# 01_USB_Isolator.net
KiCad netlist of a schematic drawn in Altium Designer
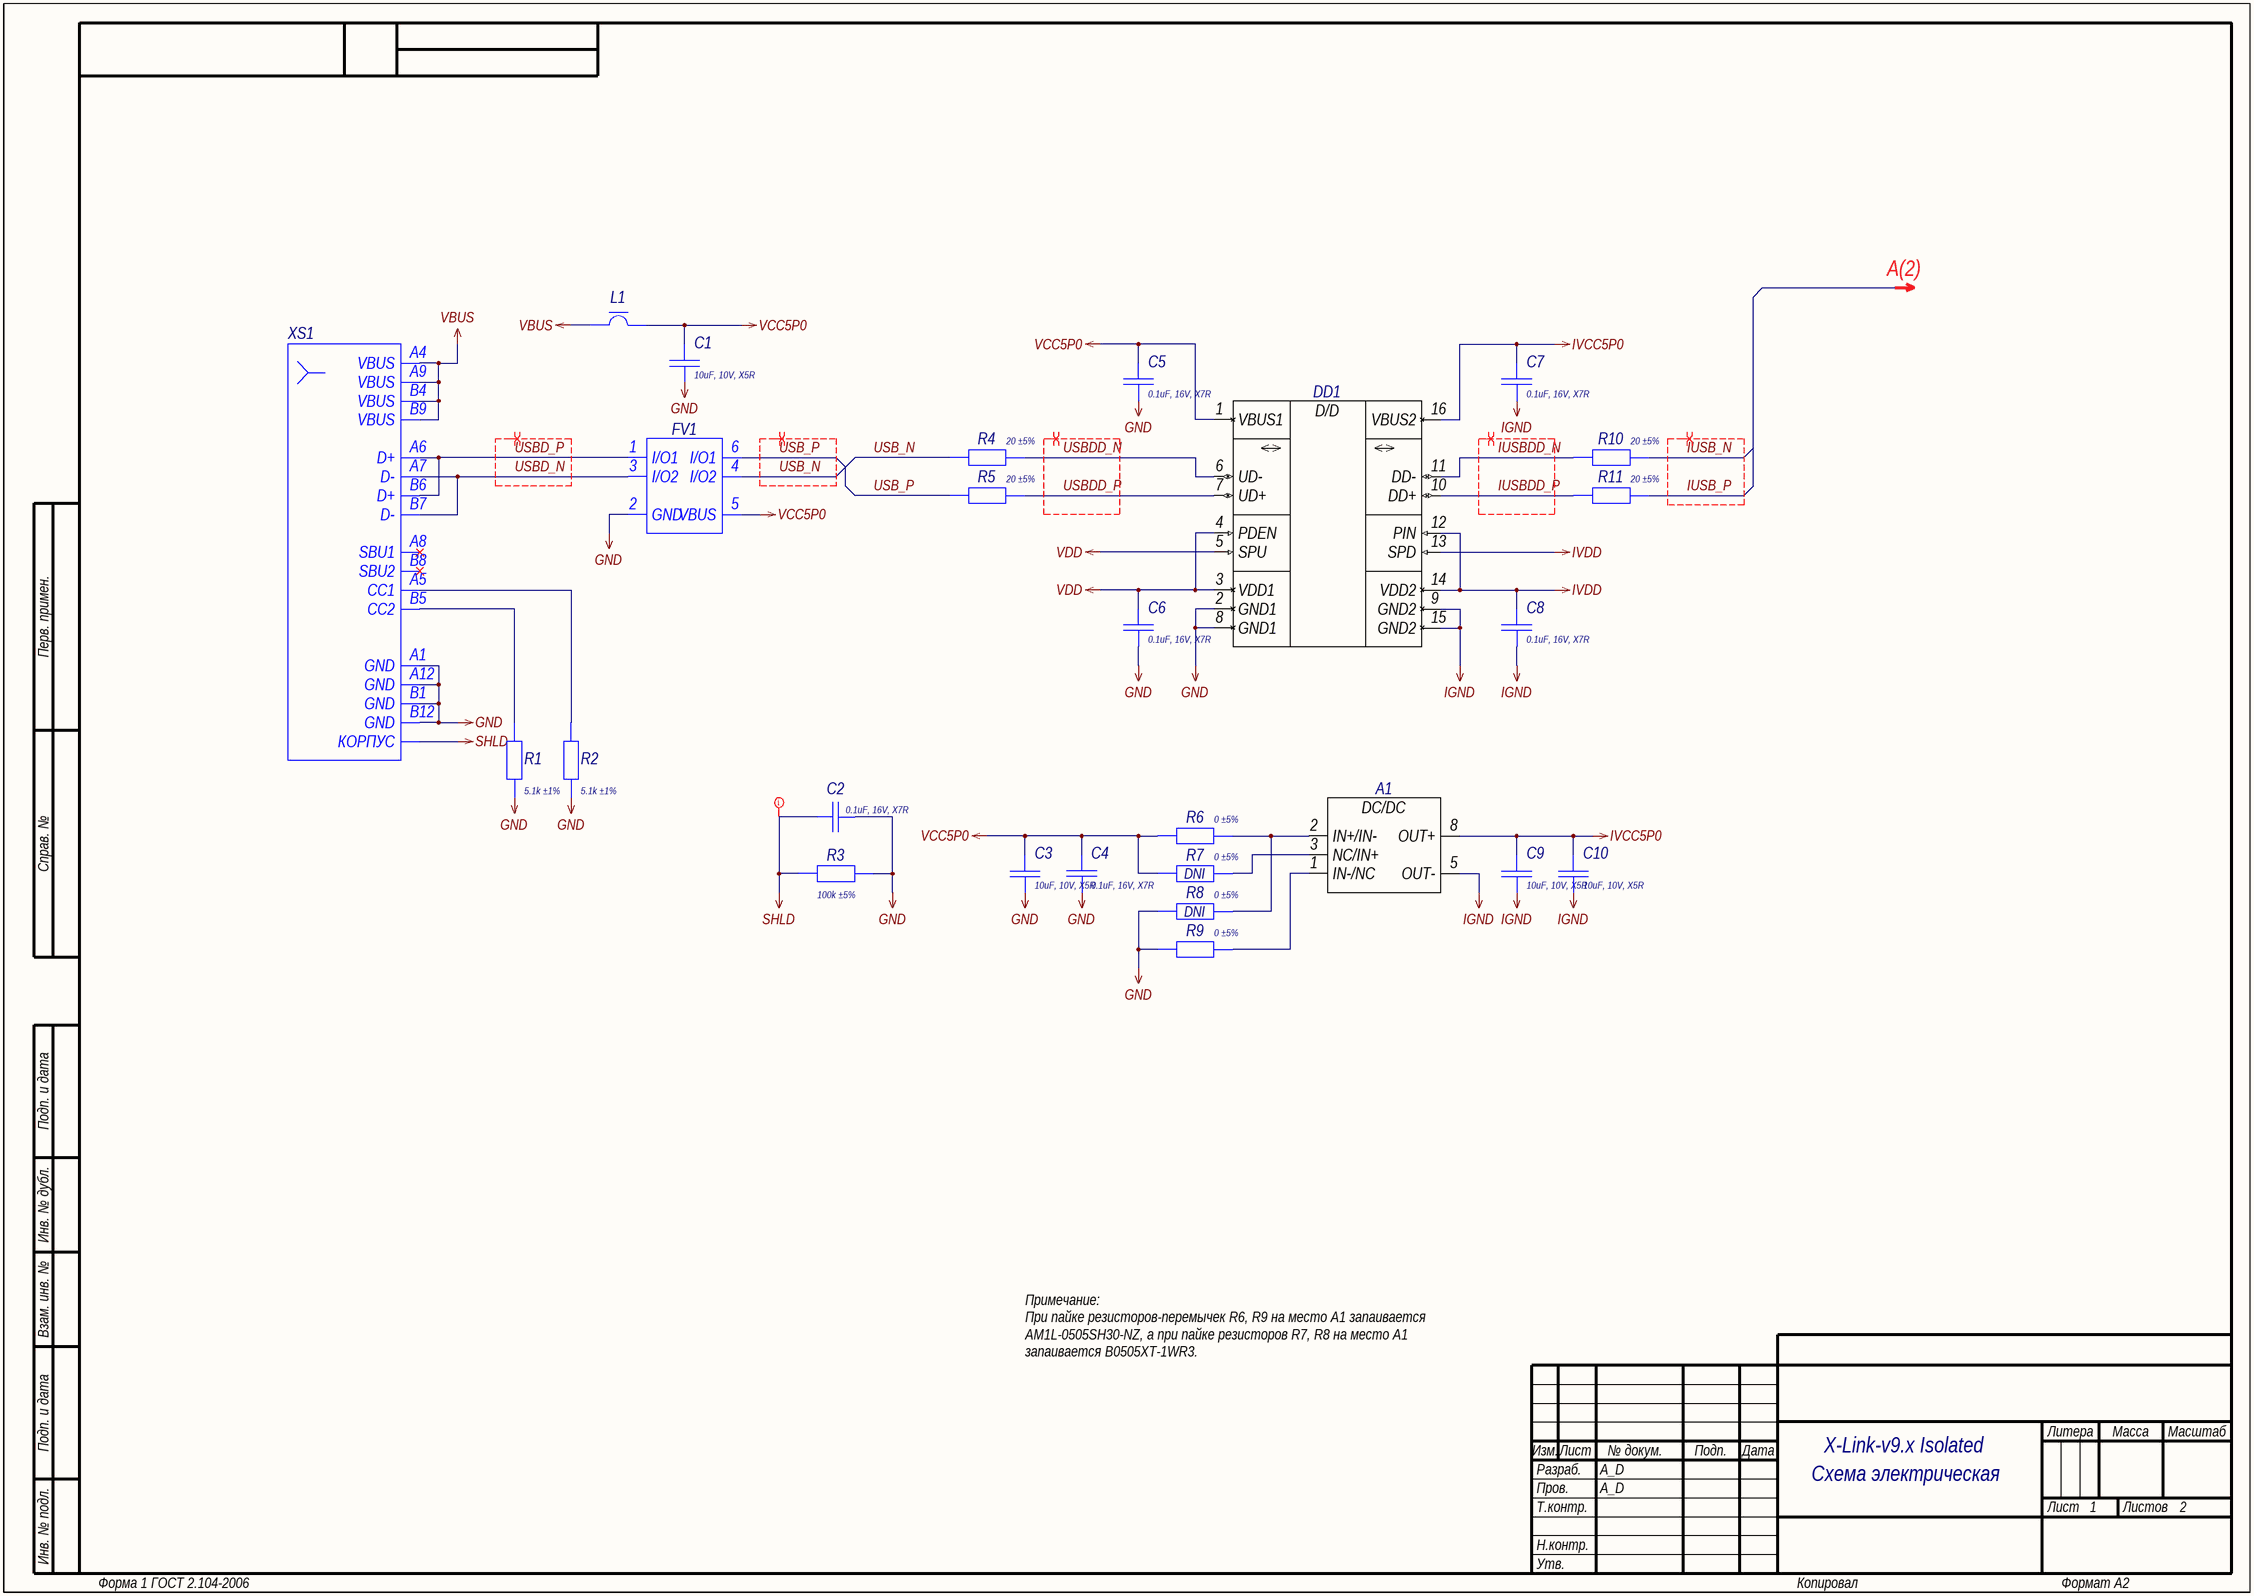
[diagram p0: 01_USB Isolator.SchDoc]

(export (version "E")
  (design (tool "Eeschema 10.0.6"))
  (components
    (comp (ref "A1")
      (value "AM1L-xxxxSH30-Series")
      (footprint "AM1L-xxxxSH30-Series")
      (fields
        (field (name "PART NUMBER") "AM1L-0505SH30-NZ")
        (field (name "MANUFACTURER") "Aimtec")
        (field (name "PUBLISHER") "Andrew Danich")
      )
      (libsource (lib "ADLib") (part "AM1L-xxxxSH30-Series"))
    )
    (comp (ref "C1")
      (value "Capacitor")
      (footprint "C0603_L")
      (fields
        (field (name "PART NUMBER") "GRM188R61A106KE69D")
        (field (name "VOLTAGE") "10V")
        (field (name "TOLERANCE") "±10%")
        (field (name "SCHEMATIC VALUE") "10uF, 10V, X5R")
        (field (name "PUBLISHER") "Andrew Danich")
      )
      (libsource (lib "ADLib") (part "Capacitor"))
    )
    (comp (ref "C2")
      (value "Capacitor")
      (footprint "C0402_L")
      (fields
        (field (name "PART NUMBER") "GCM155R71C104KA55D")
        (field (name "VOLTAGE") "16V")
        (field (name "TOLERANCE") "±10%")
        (field (name "SCHEMATIC VALUE") "0.1uF, 16V, X7R")
        (field (name "PUBLISHER") "Andrew Danich")
      )
      (libsource (lib "ADLib") (part "Capacitor"))
    )
    (comp (ref "C3")
      (value "Capacitor")
      (footprint "C0603_L")
      (fields
        (field (name "PART NUMBER") "GRM188R61A106KE69D")
        (field (name "VOLTAGE") "10V")
        (field (name "TOLERANCE") "±10%")
        (field (name "SCHEMATIC VALUE") "10uF, 10V, X5R")
        (field (name "PUBLISHER") "Andrew Danich")
      )
      (libsource (lib "ADLib") (part "Capacitor"))
    )
    (comp (ref "C4")
      (value "Capacitor")
      (footprint "C0402_L")
      (fields
        (field (name "PART NUMBER") "GCM155R71C104KA55D")
        (field (name "VOLTAGE") "16V")
        (field (name "TOLERANCE") "±10%")
        (field (name "SCHEMATIC VALUE") "0.1uF, 16V, X7R")
        (field (name "PUBLISHER") "Andrew Danich")
      )
      (libsource (lib "ADLib") (part "Capacitor"))
    )
    (comp (ref "C5")
      (value "Capacitor")
      (footprint "C0402_L")
      (fields
        (field (name "PART NUMBER") "GCM155R71C104KA55D")
        (field (name "VOLTAGE") "16V")
        (field (name "TOLERANCE") "±10%")
        (field (name "SCHEMATIC VALUE") "0.1uF, 16V, X7R")
        (field (name "PUBLISHER") "Andrew Danich")
      )
      (libsource (lib "ADLib") (part "Capacitor"))
    )
    (comp (ref "C6")
      (value "Capacitor")
      (footprint "C0402_L")
      (fields
        (field (name "PART NUMBER") "GCM155R71C104KA55D")
        (field (name "VOLTAGE") "16V")
        (field (name "TOLERANCE") "±10%")
        (field (name "SCHEMATIC VALUE") "0.1uF, 16V, X7R")
        (field (name "PUBLISHER") "Andrew Danich")
      )
      (libsource (lib "ADLib") (part "Capacitor"))
    )
    (comp (ref "C7")
      (value "Capacitor")
      (footprint "C0402_L")
      (fields
        (field (name "PART NUMBER") "GCM155R71C104KA55D")
        (field (name "VOLTAGE") "16V")
        (field (name "TOLERANCE") "±10%")
        (field (name "SCHEMATIC VALUE") "0.1uF, 16V, X7R")
        (field (name "PUBLISHER") "Andrew Danich")
      )
      (libsource (lib "ADLib") (part "Capacitor"))
    )
    (comp (ref "C8")
      (value "Capacitor")
      (footprint "C0402_L")
      (fields
        (field (name "PART NUMBER") "GCM155R71C104KA55D")
        (field (name "VOLTAGE") "16V")
        (field (name "TOLERANCE") "±10%")
        (field (name "SCHEMATIC VALUE") "0.1uF, 16V, X7R")
        (field (name "PUBLISHER") "Andrew Danich")
      )
      (libsource (lib "ADLib") (part "Capacitor"))
    )
    (comp (ref "C9")
      (value "Capacitor")
      (footprint "C0603_L")
      (fields
        (field (name "PART NUMBER") "GRM188R61A106KE69D")
        (field (name "VOLTAGE") "10V")
        (field (name "TOLERANCE") "±10%")
        (field (name "SCHEMATIC VALUE") "10uF, 10V, X5R")
        (field (name "PUBLISHER") "Andrew Danich")
      )
      (libsource (lib "ADLib") (part "Capacitor"))
    )
    (comp (ref "C10")
      (value "Capacitor")
      (footprint "C0603_L")
      (fields
        (field (name "PART NUMBER") "GRM188R61A106KE69D")
        (field (name "VOLTAGE") "10V")
        (field (name "TOLERANCE") "±10%")
        (field (name "SCHEMATIC VALUE") "10uF, 10V, X5R")
        (field (name "PUBLISHER") "Andrew Danich")
      )
      (libsource (lib "ADLib") (part "Capacitor"))
    )
    (comp (ref "DD1")
      (value "ADuMx160-Series")
      (footprint "SOIC-16_127P1030X750X265_N")
      (fields
        (field (name "PART NUMBER") "ADUM3160BRWZ")
        (field (name "MANUFACTURER") "Analog Devices")
        (field (name "PUBLISHER") "Andrew Danich")
      )
      (libsource (lib "ADLib") (part "ADuMx160-Series"))
    )
    (comp (ref "FV1")
      (value "USBLC6-2x6")
      (footprint "SOT-666_050P160X120X060_N")
      (fields
        (field (name "PART NUMBER") "USBLC6-2P6")
        (field (name "MANUFACTURER") "STMicroelectronics")
        (field (name "PUBLISHER") "Andrew Danich")
      )
      (libsource (lib "ADLib") (part "USBLC6-2x6"))
    )
    (comp (ref "L1")
      (value "FerriteBead")
      (footprint "L0402_L")
      (fields
        (field (name "PART NUMBER") "BLM15PD121SN1D")
        (field (name "TOLERANCE") "±25%")
        (field (name "MANUFACTURER") "Murata")
        (field (name "PUBLISHER") "Andrew Danich")
      )
      (libsource (lib "ADLib") (part "FerriteBead"))
    )
    (comp (ref "R1")
      (value "Resistor")
      (footprint "R0402_L")
      (fields
        (field (name "PART NUMBER") "RC0402FR-075K1L")
        (field (name "TOLERANCE") "±1%")
        (field (name "MANUFACTURER") "Yageo")
        (field (name "SCHEMATIC VALUE") "5.1k ±1%")
        (field (name "PUBLISHER") "Andrew Danich")
      )
      (libsource (lib "ADLib") (part "Resistor"))
    )
    (comp (ref "R2")
      (value "Resistor")
      (footprint "R0402_L")
      (fields
        (field (name "PART NUMBER") "RC0402FR-075K1L")
        (field (name "TOLERANCE") "±1%")
        (field (name "MANUFACTURER") "Yageo")
        (field (name "SCHEMATIC VALUE") "5.1k ±1%")
        (field (name "PUBLISHER") "Andrew Danich")
      )
      (libsource (lib "ADLib") (part "Resistor"))
    )
    (comp (ref "R3")
      (value "Resistor")
      (footprint "R0402_L")
      (fields
        (field (name "PART NUMBER") "RC0402JR-07100KL")
        (field (name "TOLERANCE") "±5%")
        (field (name "MANUFACTURER") "Yageo")
        (field (name "SCHEMATIC VALUE") "100k ±5%")
        (field (name "PUBLISHER") "Andrew Danich")
      )
      (libsource (lib "ADLib") (part "Resistor"))
    )
    (comp (ref "R4")
      (value "Resistor")
      (footprint "R0402_L")
      (fields
        (field (name "PART NUMBER") "RC0402JR-0720RL")
        (field (name "TOLERANCE") "±5%")
        (field (name "MANUFACTURER") "Yageo")
        (field (name "SCHEMATIC VALUE") "20 ±5%")
        (field (name "PUBLISHER") "Andrew Danich")
      )
      (libsource (lib "ADLib") (part "Resistor"))
    )
    (comp (ref "R5")
      (value "Resistor")
      (footprint "R0402_L")
      (fields
        (field (name "PART NUMBER") "RC0402JR-0720RL")
        (field (name "TOLERANCE") "±5%")
        (field (name "MANUFACTURER") "Yageo")
        (field (name "SCHEMATIC VALUE") "20 ±5%")
        (field (name "PUBLISHER") "Andrew Danich")
      )
      (libsource (lib "ADLib") (part "Resistor"))
    )
    (comp (ref "R6")
      (value "Resistor")
      (footprint "R0402_L")
      (fields
        (field (name "PART NUMBER") "RC0402JR-070RL")
        (field (name "TOLERANCE") "±5%")
        (field (name "MANUFACTURER") "Yageo")
        (field (name "SCHEMATIC VALUE") "0 ±5%")
        (field (name "PUBLISHER") "Andrew Danich")
      )
      (libsource (lib "ADLib") (part "Resistor"))
    )
    (comp (ref "R7")
      (value "Resistor")
      (footprint "R0402_L")
      (fields
        (field (name "PART NUMBER") "RC0402JR-070RL")
        (field (name "TOLERANCE") "±5%")
        (field (name "MANUFACTURER") "Yageo")
        (field (name "SCHEMATIC VALUE") "0 ±5%")
        (field (name "PUBLISHER") "Andrew Danich")
      )
      (libsource (lib "ADLib") (part "Resistor"))
    )
    (comp (ref "R8")
      (value "Resistor")
      (footprint "R0402_L")
      (fields
        (field (name "PART NUMBER") "RC0402JR-070RL")
        (field (name "TOLERANCE") "±5%")
        (field (name "MANUFACTURER") "Yageo")
        (field (name "SCHEMATIC VALUE") "0 ±5%")
        (field (name "PUBLISHER") "Andrew Danich")
      )
      (libsource (lib "ADLib") (part "Resistor"))
    )
    (comp (ref "R9")
      (value "Resistor")
      (footprint "R0402_L")
      (fields
        (field (name "PART NUMBER") "RC0402JR-070RL")
        (field (name "TOLERANCE") "±5%")
        (field (name "MANUFACTURER") "Yageo")
        (field (name "SCHEMATIC VALUE") "0 ±5%")
        (field (name "PUBLISHER") "Andrew Danich")
      )
      (libsource (lib "ADLib") (part "Resistor"))
    )
    (comp (ref "R10")
      (value "Resistor")
      (footprint "R0402_L")
      (fields
        (field (name "PART NUMBER") "RC0402JR-0720RL")
        (field (name "TOLERANCE") "±5%")
        (field (name "MANUFACTURER") "Yageo")
        (field (name "SCHEMATIC VALUE") "20 ±5%")
        (field (name "PUBLISHER") "Andrew Danich")
      )
      (libsource (lib "ADLib") (part "Resistor"))
    )
    (comp (ref "R11")
      (value "Resistor")
      (footprint "R0402_L")
      (fields
        (field (name "PART NUMBER") "RC0402JR-0720RL")
        (field (name "TOLERANCE") "±5%")
        (field (name "MANUFACTURER") "Yageo")
        (field (name "SCHEMATIC VALUE") "20 ±5%")
        (field (name "PUBLISHER") "Andrew Danich")
      )
      (libsource (lib "ADLib") (part "Resistor"))
    )
    (comp (ref "XS1")
      (value "Text")
      (footprint "U262-161N-4BVC11")
      (fields
        (field (name "PART NUMBER") "U262-161N-4BVC11")
        (field (name "MANUFACTURER") "XKB Enterprise")
        (field (name "PUBLISHER") "Andrew Danich")
      )
      (libsource (lib "ADLib") (part "Con-USB_C-F-16P"))
    )
  )
  (nets
    (net (code "1") (name "/IUSBDD_N") (class "Default")
      (node (ref "DD1") (pin "11") (pinfunction "DD-_11") (pintype "bidirectional"))
      (node (ref "R10") (pin "1") (pinfunction "1_1") (pintype "passive"))
    )
    (net (code "2") (name "/IUSBDD_P") (class "Default")
      (node (ref "DD1") (pin "10") (pinfunction "DD+_10") (pintype "bidirectional"))
      (node (ref "R11") (pin "1") (pinfunction "1_1") (pintype "passive"))
    )
    (net (code "3") (name "/IUSB_N") (class "Default")
      (node (ref "R10") (pin "2") (pinfunction "2_2") (pintype "passive"))
    )
    (net (code "4") (name "/IUSB_P") (class "Default")
      (node (ref "R11") (pin "2") (pinfunction "2_2") (pintype "passive"))
    )
    (net (code "5") (name "/USBDD_N") (class "Default")
      (node (ref "DD1") (pin "6") (pinfunction "UD-_6") (pintype "bidirectional"))
      (node (ref "R4") (pin "2") (pinfunction "2_2") (pintype "passive"))
    )
    (net (code "6") (name "/USBDD_P") (class "Default")
      (node (ref "DD1") (pin "7") (pinfunction "UD+_7") (pintype "bidirectional"))
      (node (ref "R5") (pin "2") (pinfunction "2_2") (pintype "passive"))
    )
    (net (code "7") (name "/USBD_N") (class "Default")
      (node (ref "FV1") (pin "3") (pinfunction "I/O2_3") (pintype "passive"))
      (node (ref "XS1") (pin "A7") (pinfunction "D-_A7") (pintype "passive"))
      (node (ref "XS1") (pin "B7") (pinfunction "D-_B7") (pintype "passive"))
    )
    (net (code "8") (name "/USBD_P") (class "Default")
      (node (ref "FV1") (pin "1") (pinfunction "I/O1_1") (pintype "passive"))
      (node (ref "XS1") (pin "A6") (pinfunction "D+_A6") (pintype "passive"))
      (node (ref "XS1") (pin "B6") (pinfunction "D+_B6") (pintype "passive"))
    )
    (net (code "9") (name "/USB_N") (class "Default")
      (node (ref "FV1") (pin "4") (pinfunction "I/O2_4") (pintype "passive"))
      (node (ref "R4") (pin "1") (pinfunction "1_1") (pintype "passive"))
    )
    (net (code "10") (name "/USB_P") (class "Default")
      (node (ref "FV1") (pin "6") (pinfunction "I/O1_6") (pintype "passive"))
      (node (ref "R5") (pin "1") (pinfunction "1_1") (pintype "passive"))
    )
    (net (code "11") (name "GND") (class "Default")
      (node (ref "C1") (pin "1") (pinfunction "1_1") (pintype "passive"))
      (node (ref "C2") (pin "1") (pinfunction "1_1") (pintype "passive"))
      (node (ref "C3") (pin "1") (pinfunction "1_1") (pintype "passive"))
      (node (ref "C4") (pin "2") (pinfunction "2_2") (pintype "passive"))
      (node (ref "C5") (pin "2") (pinfunction "2_2") (pintype "passive"))
      (node (ref "C6") (pin "2") (pinfunction "2_2") (pintype "passive"))
      (node (ref "DD1") (pin "2") (pinfunction "GND1_2") (pintype "power_in"))
      (node (ref "DD1") (pin "8") (pinfunction "GND1_8") (pintype "power_in"))
      (node (ref "FV1") (pin "2") (pinfunction "GND_2") (pintype "passive"))
      (node (ref "R1") (pin "1") (pinfunction "1_1") (pintype "passive"))
      (node (ref "R2") (pin "1") (pinfunction "1_1") (pintype "passive"))
      (node (ref "R3") (pin "2") (pinfunction "2_2") (pintype "passive"))
      (node (ref "R8") (pin "1") (pinfunction "1_1") (pintype "passive"))
      (node (ref "R9") (pin "1") (pinfunction "1_1") (pintype "passive"))
      (node (ref "XS1") (pin "A1") (pinfunction "GND_A1") (pintype "passive"))
      (node (ref "XS1") (pin "A12") (pinfunction "GND_A12") (pintype "passive"))
      (node (ref "XS1") (pin "B1") (pinfunction "GND_B1") (pintype "passive"))
      (node (ref "XS1") (pin "B12") (pinfunction "GND_B12") (pintype "passive"))
    )
    (net (code "12") (name "IGND") (class "Default")
      (node (ref "A1") (pin "5") (pinfunction "OUT-_5") (pintype "power_in"))
      (node (ref "C10") (pin "1") (pinfunction "1_1") (pintype "passive"))
      (node (ref "C7") (pin "2") (pinfunction "2_2") (pintype "passive"))
      (node (ref "C8") (pin "2") (pinfunction "2_2") (pintype "passive"))
      (node (ref "C9") (pin "1") (pinfunction "1_1") (pintype "passive"))
      (node (ref "DD1") (pin "15") (pinfunction "GND2_15") (pintype "power_in"))
      (node (ref "DD1") (pin "9") (pinfunction "GND2_9") (pintype "power_in"))
    )
    (net (code "13") (name "IVCC5P0") (class "Default")
      (node (ref "A1") (pin "8") (pinfunction "OUT+_8") (pintype "power_in"))
      (node (ref "C10") (pin "2") (pinfunction "2_2") (pintype "passive"))
      (node (ref "C7") (pin "1") (pinfunction "1_1") (pintype "passive"))
      (node (ref "C9") (pin "2") (pinfunction "2_2") (pintype "passive"))
      (node (ref "DD1") (pin "16") (pinfunction "VBUS2_16") (pintype "power_in"))
    )
    (net (code "14") (name "IVDD") (class "Default")
      (node (ref "C8") (pin "1") (pinfunction "1_1") (pintype "passive"))
      (node (ref "DD1") (pin "12") (pinfunction "PIN_12") (pintype "input"))
      (node (ref "DD1") (pin "13") (pinfunction "SPD_13") (pintype "input"))
      (node (ref "DD1") (pin "14") (pinfunction "VDD2_14") (pintype "power_in"))
    )
    (net (code "15") (name "Net-(A1-IN+{slash}IN-)") (class "Default")
      (node (ref "A1") (pin "2") (pinfunction "IN+/IN-_2") (pintype "power_in"))
      (node (ref "R6") (pin "2") (pinfunction "2_2") (pintype "passive"))
      (node (ref "R8") (pin "2") (pinfunction "2_2") (pintype "passive"))
    )
    (net (code "16") (name "Net-(A1-IN-{slash}NC)") (class "Default")
      (node (ref "A1") (pin "1") (pinfunction "IN-/NC_1") (pintype "power_in"))
      (node (ref "R9") (pin "2") (pinfunction "2_2") (pintype "passive"))
    )
    (net (code "17") (name "Net-(A1-NC{slash}IN+)") (class "Default")
      (node (ref "A1") (pin "3") (pinfunction "NC/IN+_3") (pintype "passive"))
      (node (ref "R7") (pin "2") (pinfunction "2_2") (pintype "passive"))
    )
    (net (code "18") (name "Net-(XS1-CC1)") (class "Default")
      (node (ref "R2") (pin "2") (pinfunction "2_2") (pintype "passive"))
      (node (ref "XS1") (pin "A5") (pinfunction "CC1_A5") (pintype "passive"))
    )
    (net (code "19") (name "Net-(XS1-CC2)") (class "Default")
      (node (ref "R1") (pin "2") (pinfunction "2_2") (pintype "passive"))
      (node (ref "XS1") (pin "B5") (pinfunction "CC2_B5") (pintype "passive"))
    )
    (net (code "20") (name "SHLD") (class "Default")
      (node (ref "C2") (pin "2") (pinfunction "2_2") (pintype "passive"))
      (node (ref "R3") (pin "1") (pinfunction "1_1") (pintype "passive"))
      (node (ref "XS1") (pin "SH") (pinfunction "КОРПУС_SH") (pintype "passive"))
    )
    (net (code "21") (name "VBUS") (class "Default")
      (node (ref "L1") (pin "1") (pinfunction "1_1") (pintype "passive"))
      (node (ref "XS1") (pin "A4") (pinfunction "VBUS_A4") (pintype "passive"))
      (node (ref "XS1") (pin "A9") (pinfunction "VBUS_A9") (pintype "passive"))
      (node (ref "XS1") (pin "B4") (pinfunction "VBUS_B4") (pintype "passive"))
      (node (ref "XS1") (pin "B9") (pinfunction "VBUS_B9") (pintype "passive"))
    )
    (net (code "22") (name "VCC5P0") (class "Default")
      (node (ref "C1") (pin "2") (pinfunction "2_2") (pintype "passive"))
      (node (ref "C3") (pin "2") (pinfunction "2_2") (pintype "passive"))
      (node (ref "C4") (pin "1") (pinfunction "1_1") (pintype "passive"))
      (node (ref "C5") (pin "1") (pinfunction "1_1") (pintype "passive"))
      (node (ref "DD1") (pin "1") (pinfunction "VBUS1_1") (pintype "power_in"))
      (node (ref "FV1") (pin "5") (pinfunction "VBUS_5") (pintype "passive"))
      (node (ref "L1") (pin "2") (pinfunction "2_2") (pintype "passive"))
      (node (ref "R6") (pin "1") (pinfunction "1_1") (pintype "passive"))
      (node (ref "R7") (pin "1") (pinfunction "1_1") (pintype "passive"))
    )
    (net (code "23") (name "VDD") (class "Default")
      (node (ref "C6") (pin "1") (pinfunction "1_1") (pintype "passive"))
      (node (ref "DD1") (pin "3") (pinfunction "VDD1_3") (pintype "power_in"))
      (node (ref "DD1") (pin "4") (pinfunction "PDEN_4") (pintype "input"))
      (node (ref "DD1") (pin "5") (pinfunction "SPU_5") (pintype "input"))
    )
    (net (code "24") (name "unconnected-(XS1-SBU1-PadA8)") (class "Default")
      (node (ref "XS1") (pin "A8") (pinfunction "SBU1_A8") (pintype "passive+no_connect"))
    )
    (net (code "25") (name "unconnected-(XS1-SBU2-PadB8)") (class "Default")
      (node (ref "XS1") (pin "B8") (pinfunction "SBU2_B8") (pintype "passive+no_connect"))
    )
  )
)
